# Power.net
KiCad netlist of a schematic drawn in Altium Designer
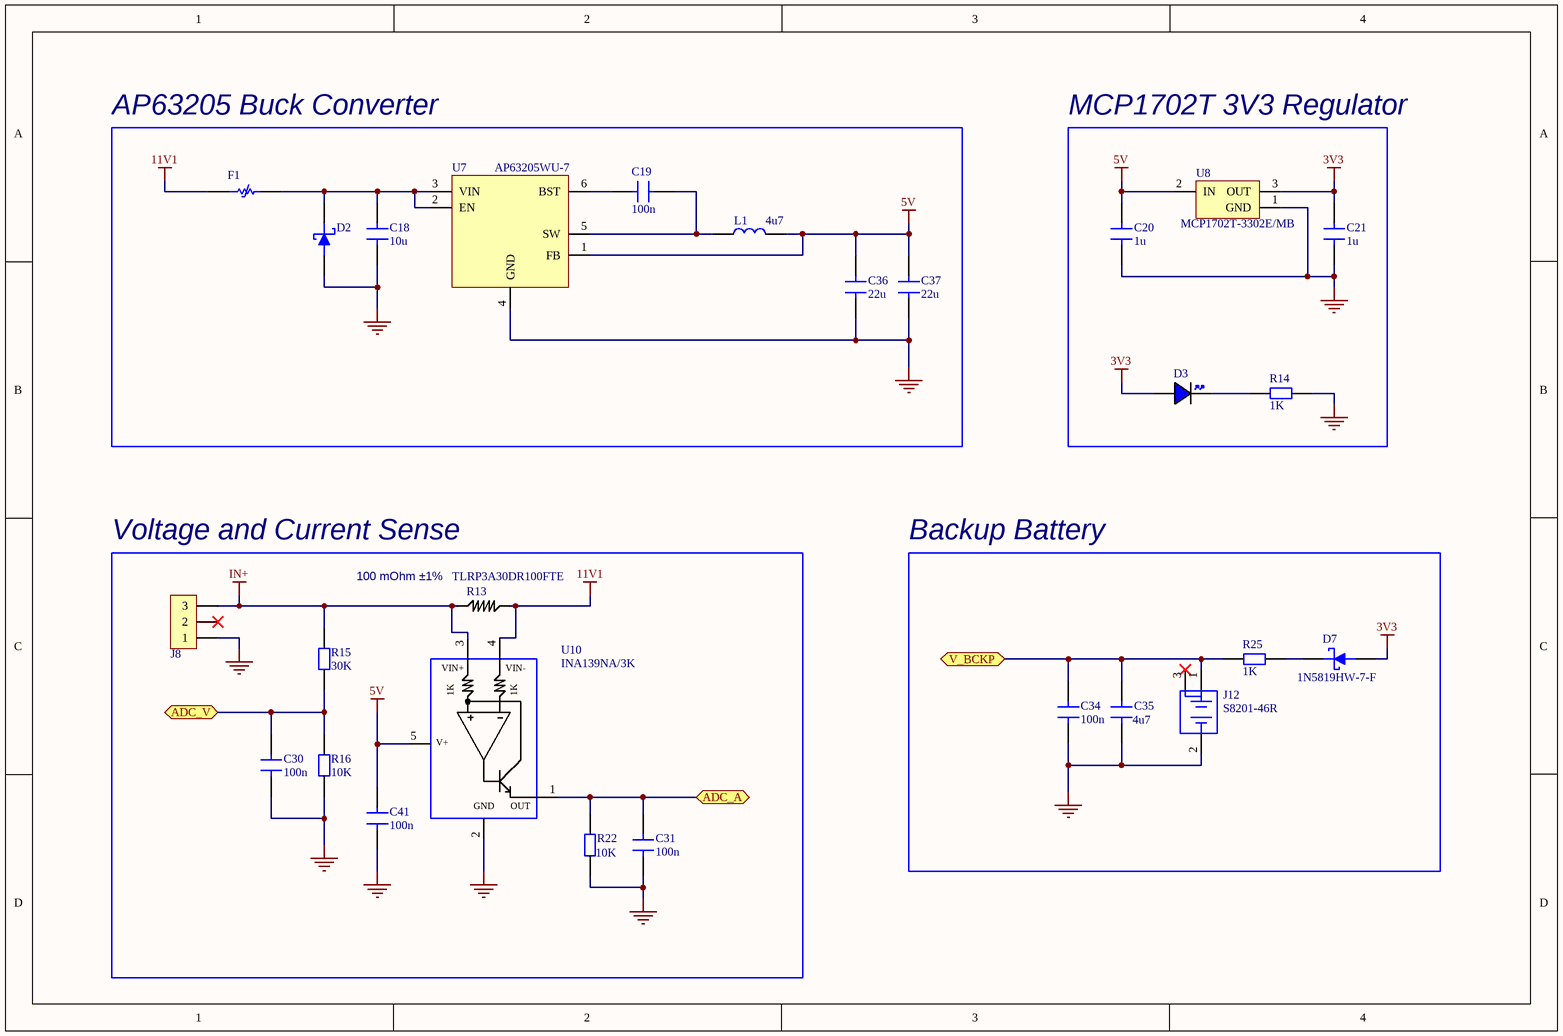
[diagram p0: Power.SchDoc]

(export (version "E")
  (design (tool "Eeschema 10.0.6"))
  (components
    (comp (ref "C18")
      (value "10u")
      (footprint "CAP 1210")
      (description "Capacitor SMD 1210 50V")
      (libsource (lib "Schlib") (part "CAP 1210 50V"))
    )
    (comp (ref "C19")
      (value "100n")
      (footprint "CAP 0805")
      (description "Capacitor SMD 0805 50V")
      (libsource (lib "Schlib") (part "CAP 0805 50V"))
    )
    (comp (ref "C20")
      (value "1u")
      (footprint "CAP 0805")
      (description "Capacitor SMD 0805 50V")
      (libsource (lib "Schlib") (part "CAP 0805 50V"))
    )
    (comp (ref "C21")
      (value "1u")
      (footprint "CAP 0805")
      (description "Capacitor SMD 0805 50V")
      (libsource (lib "Schlib") (part "CAP 0805 50V"))
    )
    (comp (ref "C30")
      (value "100n")
      (footprint "CAP 0805")
      (description "Capacitor SMD 0805 50V")
      (libsource (lib "Schlib") (part "CAP 0805 50V"))
    )
    (comp (ref "C31")
      (value "100n")
      (footprint "CAP 0805")
      (description "Capacitor SMD 0805 50V")
      (libsource (lib "Schlib") (part "CAP 0805 50V"))
    )
    (comp (ref "C34")
      (value "100n")
      (footprint "CAP 0603")
      (description "Capacitor SMD 0603 50V")
      (libsource (lib "Schlib") (part "CAP 0603 50V"))
    )
    (comp (ref "C35")
      (value "4u7")
      (footprint "CAP 0805")
      (description "Capacitor SMD 0805 25V")
      (libsource (lib "Schlib") (part "CAP 0805 25V"))
    )
    (comp (ref "C36")
      (value "22u")
      (footprint "CAP 1210")
      (description "Capacitor SMD 1210 25V")
      (libsource (lib "Schlib") (part "CAP 1210 25V"))
    )
    (comp (ref "C37")
      (value "22u")
      (footprint "CAP 1210")
      (description "Capacitor SMD 1210 25V")
      (libsource (lib "Schlib") (part "CAP 1210 25V"))
    )
    (comp (ref "C41")
      (value "100n")
      (footprint "CAP 0805")
      (description "Capacitor SMD 0805 50V")
      (libsource (lib "Schlib") (part "CAP 0805 50V"))
    )
    (comp (ref "D2")
      (value "SMBJ14CA")
      (footprint "SMBJ12CA-13-F")
      (description "TVS DIODE 14VWM 23.2VC DO214AA")
      (fields (field (name "MANUFACTURER") "Littelfuse") (field (name "VOLTAGE") "14V"))
      (libsource (lib "Schlib") (part "SMBJ14CA"))
    )
    (comp (ref "D3")
      (value "LED 0805 BLUE")
      (footprint "LED 0805 BLUE")
      (description "LED 0805 GREEN SMD")
      (libsource (lib "Schlib") (part "LED 0805 BLUE"))
    )
    (comp (ref "D7")
      (value "1N5819HW-7-F")
      (footprint "1N5819HW-7-F")
      (description "Rectifier Diode, Schottky, 1 Phase, 1 Element, 1A, 40V V(RRM), Silicon")
      (fields (field (name "MANUFACTURER") "Diodes"))
      (libsource (lib "Schlib") (part "1N5819HW-7-F"))
    )
    (comp (ref "F1")
      (value "MF-MSMF075/24-2")
      (footprint "0ZCG0075FF2C")
      (fields (field (name "MANUFACTURER") "Bourns"))
      (libsource (lib "Schlib") (part "MF-MSMF075/24-2"))
    )
    (comp (ref "J8")
      (value "JST B3B-XH-A")
      (footprint "JST_B3B-XH-A")
      (description "Connector Header, XH Series, 3 Position, 2.50mm, Through Hole, Press-Fit, Solder, Natural")
      (fields
        (field (name "MANUFACTURER") "JST")
        (field (name "MANUFACTURER PART NUMBER") "B3B-XH-A(LF)(SN)")
      )
      (libsource (lib "Schlib") (part "JST B3B-XH-A"))
    )
    (comp (ref "J12")
      (value "S8201-46R")
      (footprint "S8201-46R")
      (description "Battery Holder, Coin Cell, 1225, Smd Rohs Compliant: Yes ¦Harwin S8201-46R")
      (fields (field (name "MANUFACTURER") "Harwin"))
      (libsource (lib "Schlib") (part "S8201-46R"))
    )
    (comp (ref "L1")
      (value "4u7")
      (footprint "IHLP2020CZER4R7M11")
      (description "Inductor Power Shielded Wirewound 4.7uH 20% 100KHz Powdered Iron 4.5A 60mOhm DCR 2020 T/R")
      (fields
        (field (name "MANUFACTURER") "Vishay")
        (field (name "MANUFACTURER PART NUMBER") "IHLP2020CZER4R7M11")
      )
      (libsource (lib "Schlib") (part "IHLP2020CZER4R7M11"))
    )
    (comp (ref "R13")
      (value "TLRP3A30DR100FTE")
      (footprint "RES 2512")
      (description "Res, 0R1, 1%, 3W, Metal Strip, SMD Rohs Compliant: Yes")
      (fields (field (name "MANUFACTURER") "TE Connectivity"))
      (libsource (lib "Schlib") (part "TLRP3A30DR100FTE"))
    )
    (comp (ref "R14")
      (value "1K")
      (footprint "RES 0603")
      (description "Resistor SMD 0603")
      (libsource (lib "Schlib") (part "RES 0603"))
    )
    (comp (ref "R15")
      (value "30K")
      (footprint "RES 0805")
      (description "Resistor SMD 0805")
      (libsource (lib "Schlib") (part "RES 0805"))
    )
    (comp (ref "R16")
      (value "10K")
      (footprint "RES 0805")
      (description "Resistor SMD 0805")
      (libsource (lib "Schlib") (part "RES 0805"))
    )
    (comp (ref "R22")
      (value "10K")
      (footprint "RES 0805")
      (description "Resistor SMD 0805")
      (libsource (lib "Schlib") (part "RES 0805"))
    )
    (comp (ref "R25")
      (value "1K")
      (footprint "RES 0603")
      (description "Resistor SMD 0603")
      (libsource (lib "Schlib") (part "RES 0603"))
    )
    (comp (ref "U7")
      (value "AP63205WU-7")
      (footprint "AP63205")
      (description "AP63205 Series 32 V 2 A 1.1 MHz Synchronous Buck Converter -TSOT-26")
      (fields (field (name "MANUFACTURER") "Diodes"))
      (libsource (lib "Schlib") (part "AP63205WU-7"))
    )
    (comp (ref "U8")
      (value "MCP1702T-3302E/MB")
      (footprint "MCP1702T-3302E/MB")
      (description "LDO Regulator Pos 3.3V 0.25A Automotive 4-Pin(3+Tab) SOT-89 T/R")
      (fields (field (name "MANUFACTURER") "Microchip"))
      (libsource (lib "Schlib") (part "MCP1702T-3302E/MB"))
    )
    (comp (ref "U10")
      (value "INA139NA/3K")
      (footprint "INA139NA")
      (description "2.7 to 36V, 440kHz Variable gain current sense amplifier 5-SOT-23 -40 to 125")
      (fields (field (name "MANUFACTURER") "Texas Instruments"))
      (libsource (lib "Schlib") (part "INA139NA/3K"))
    )
  )
  (nets
    (net (code "1") (name "/ADC_A") (class "Default")
      (node (ref "C31") (pin "2") (pinfunction "2_2") (pintype "passive"))
      (node (ref "R22") (pin "2") (pinfunction "2_2") (pintype "passive"))
      (node (ref "U10") (pin "1") (pinfunction "OUT_1") (pintype "passive"))
    )
    (net (code "2") (name "/ADC_V") (class "Default")
      (node (ref "C30") (pin "2") (pinfunction "2_2") (pintype "passive"))
      (node (ref "R15") (pin "1") (pinfunction "1_1") (pintype "passive"))
      (node (ref "R16") (pin "2") (pinfunction "2_2") (pintype "passive"))
    )
    (net (code "3") (name "/V_BCKP") (class "Default")
      (node (ref "C34") (pin "2") (pinfunction "2_2") (pintype "passive"))
      (node (ref "C35") (pin "2") (pinfunction "2_2") (pintype "passive"))
      (node (ref "J12") (pin "1") (pinfunction "+_1") (pintype "passive"))
      (node (ref "R25") (pin "1") (pinfunction "1_1") (pintype "passive"))
    )
    (net (code "4") (name "3V3") (class "Default")
      (node (ref "C21") (pin "2") (pinfunction "2_2") (pintype "passive"))
      (node (ref "D3") (pin "A") (pinfunction "A_A") (pintype "passive"))
      (node (ref "D7") (pin "C") (pintype "passive"))
      (node (ref "U8") (pin "3") (pinfunction "OUT_3") (pintype "passive"))
    )
    (net (code "5") (name "5V") (class "Default")
      (node (ref "C20") (pin "2") (pinfunction "2_2") (pintype "passive"))
      (node (ref "C36") (pin "2") (pinfunction "2_2") (pintype "passive"))
      (node (ref "C37") (pin "2") (pinfunction "2_2") (pintype "passive"))
      (node (ref "C41") (pin "2") (pinfunction "2_2") (pintype "passive"))
      (node (ref "L1") (pin "2") (pintype "passive"))
      (node (ref "U10") (pin "5") (pinfunction "V+_5") (pintype "passive"))
      (node (ref "U7") (pin "1") (pinfunction "FB_1") (pintype "passive"))
      (node (ref "U8") (pin "2") (pinfunction "IN_2") (pintype "passive"))
    )
    (net (code "6") (name "11V1") (class "Default")
      (node (ref "F1") (pin "1") (pintype "passive"))
      (node (ref "R13") (pin "1") (pinfunction "1_1") (pintype "passive"))
      (node (ref "U10") (pin "4") (pinfunction "VIN+_4") (pintype "passive"))
    )
    (net (code "7") (name "GND") (class "Default")
      (node (ref "C18") (pin "1") (pinfunction "1_1") (pintype "passive"))
      (node (ref "C20") (pin "1") (pinfunction "1_1") (pintype "passive"))
      (node (ref "C21") (pin "1") (pinfunction "1_1") (pintype "passive"))
      (node (ref "C30") (pin "1") (pinfunction "1_1") (pintype "passive"))
      (node (ref "C31") (pin "1") (pinfunction "1_1") (pintype "passive"))
      (node (ref "C34") (pin "1") (pinfunction "1_1") (pintype "passive"))
      (node (ref "C35") (pin "1") (pinfunction "1_1") (pintype "passive"))
      (node (ref "C36") (pin "1") (pinfunction "1_1") (pintype "passive"))
      (node (ref "C37") (pin "1") (pinfunction "1_1") (pintype "passive"))
      (node (ref "C41") (pin "1") (pinfunction "1_1") (pintype "passive"))
      (node (ref "D2") (pin "1") (pintype "passive"))
      (node (ref "J12") (pin "2") (pinfunction "-_2") (pintype "passive"))
      (node (ref "J8") (pin "1") (pinfunction "1_1") (pintype "passive"))
      (node (ref "R14") (pin "2") (pinfunction "2_2") (pintype "passive"))
      (node (ref "R16") (pin "1") (pinfunction "1_1") (pintype "passive"))
      (node (ref "R22") (pin "1") (pinfunction "1_1") (pintype "passive"))
      (node (ref "U10") (pin "2") (pinfunction "GND_2") (pintype "passive"))
      (node (ref "U7") (pin "4") (pinfunction "GND_4") (pintype "passive"))
      (node (ref "U8") (pin "1") (pinfunction "GND_1") (pintype "passive"))
    )
    (net (code "8") (name "IN+") (class "Default")
      (node (ref "J8") (pin "3") (pinfunction "3_3") (pintype "passive"))
      (node (ref "R13") (pin "2") (pinfunction "2_2") (pintype "passive"))
      (node (ref "R15") (pin "2") (pinfunction "2_2") (pintype "passive"))
      (node (ref "U10") (pin "3") (pinfunction "VIN+_3") (pintype "passive"))
    )
    (net (code "9") (name "Net-(D3-PadK)") (class "Default")
      (node (ref "D3") (pin "K") (pinfunction "K_K") (pintype "passive"))
      (node (ref "R14") (pin "1") (pinfunction "1_1") (pintype "passive"))
    )
    (net (code "10") (name "Net-(D7-PadA)") (class "Default")
      (node (ref "D7") (pin "A") (pintype "passive"))
      (node (ref "R25") (pin "2") (pinfunction "2_2") (pintype "passive"))
    )
    (net (code "11") (name "Net-(U7-BST)") (class "Default")
      (node (ref "C19") (pin "2") (pinfunction "2_2") (pintype "passive"))
      (node (ref "U7") (pin "6") (pinfunction "BST_6") (pintype "passive"))
    )
    (net (code "12") (name "Net-(U7-EN)") (class "Default")
      (node (ref "C18") (pin "2") (pinfunction "2_2") (pintype "passive"))
      (node (ref "D2") (pin "2") (pintype "passive"))
      (node (ref "F1") (pin "2") (pintype "passive"))
      (node (ref "U7") (pin "2") (pinfunction "EN_2") (pintype "passive"))
      (node (ref "U7") (pin "3") (pinfunction "VIN_3") (pintype "passive"))
    )
    (net (code "13") (name "Net-(U7-SW)") (class "Default")
      (node (ref "C19") (pin "1") (pinfunction "1_1") (pintype "passive"))
      (node (ref "L1") (pin "1") (pintype "passive"))
      (node (ref "U7") (pin "5") (pinfunction "SW_5") (pintype "passive"))
    )
    (net (code "14") (name "unconnected-(J8-Pad2)") (class "Default")
      (node (ref "J8") (pin "2") (pinfunction "2_2") (pintype "passive+no_connect"))
    )
    (net (code "15") (name "unconnected-(J12-+-Pad3)") (class "Default")
      (node (ref "J12") (pin "3") (pinfunction "+_3") (pintype "passive+no_connect"))
    )
  )
)
